# SensorStick.net
KiCad netlist of a schematic drawn in EAGLE
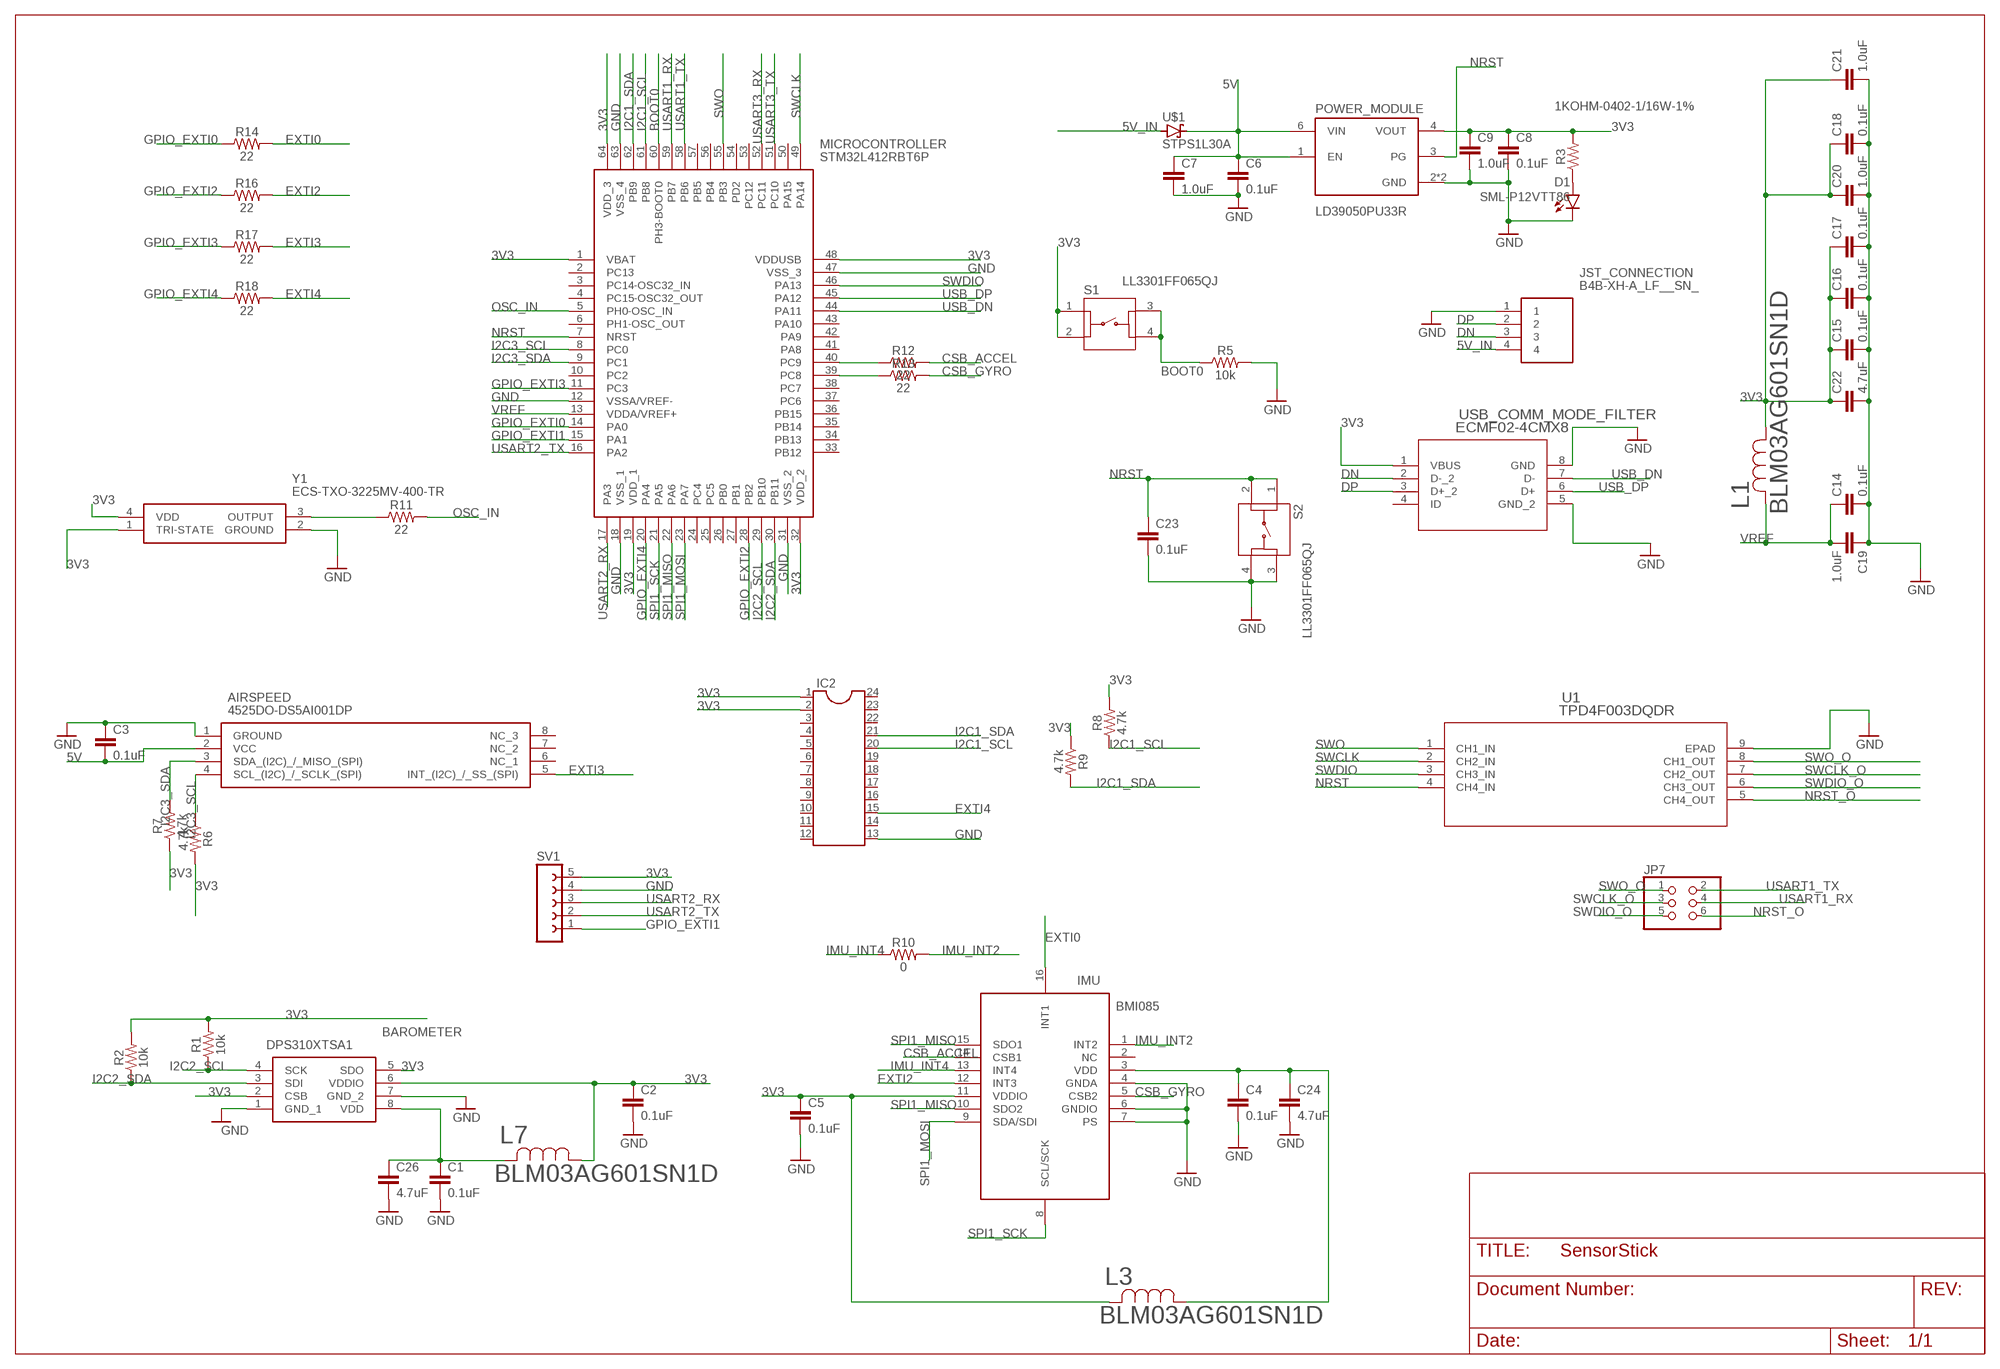
[diagram p0: schematic, sheet 1]

(export (version "E")
  (design (tool "Eeschema 10.0.6"))
  (components
    (comp (ref "AIRSPEED")
      (value "4525DO-DS5AI001DP")
      (footprint "eagle-import:4525DO-DS...P")
      (fields (field (name "MOUSER_PART_NUMBER") "824-4525DODS5AI001DP"))
      (libsource (lib "eagle-import") (part "4525DO-DS5AI001DP"))
    )
    (comp (ref "BAROMETER")
      (value "DPS310XTSA1")
      (footprint "eagle-import:DPS310XTSA1")
      (fields (field (name "MOUSER_PART_NUMBER") "726-DPS310XTSA1"))
      (libsource (lib "eagle-import") (part "DPS310XTSA1"))
    )
    (comp (ref "C1")
      (value "0.1uF")
      (footprint "eagle-import:0402")
      (libsource (lib "eagle-import") (part "0.1UF-0402-6.3V-10%-X7R"))
    )
    (comp (ref "C2")
      (value "0.1uF")
      (footprint "eagle-import:0402")
      (libsource (lib "eagle-import") (part "0.1UF-0402-6.3V-10%-X7R"))
    )
    (comp (ref "C3")
      (value "0.1uF")
      (footprint "eagle-import:0402")
      (fields (field (name "SPICEPREFIX") "C"))
      (libsource (lib "eagle-import") (part "0.1UF-0402-6.3V-10%-X7R"))
    )
    (comp (ref "C4")
      (value "0.1uF")
      (footprint "eagle-import:0402")
      (libsource (lib "eagle-import") (part "0.1UF-0402-6.3V-10%-X7R"))
    )
    (comp (ref "C5")
      (value "0.1uF")
      (footprint "eagle-import:0402")
      (libsource (lib "eagle-import") (part "0.1UF-0402-6.3V-10%-X7R"))
    )
    (comp (ref "C6")
      (value "0.1uF")
      (footprint "eagle-import:0402")
      (libsource (lib "eagle-import") (part "0.1UF-0402-6.3V-10%-X7R"))
    )
    (comp (ref "C7")
      (value "1.0uF")
      (footprint "eagle-import:0402")
      (libsource (lib "eagle-import") (part "1.0UF-0402-16V-10%"))
    )
    (comp (ref "C8")
      (value "0.1uF")
      (footprint "eagle-import:0402")
      (libsource (lib "eagle-import") (part "0.1UF-0402-6.3V-10%-X7R"))
    )
    (comp (ref "C9")
      (value "1.0uF")
      (footprint "eagle-import:0402")
      (libsource (lib "eagle-import") (part "1.0UF-0402-16V-10%"))
    )
    (comp (ref "C14")
      (value "0.1uF")
      (footprint "eagle-import:0603")
      (libsource (lib "eagle-import") (part "SparkFun-Capacitors_510_0.1UF-0603-25V-5%"))
    )
    (comp (ref "C15")
      (value "0.1uF")
      (footprint "eagle-import:0603")
      (libsource (lib "eagle-import") (part "SparkFun-Capacitors_510_0.1UF-0603-25V-5%"))
    )
    (comp (ref "C16")
      (value "0.1uF")
      (footprint "eagle-import:0603")
      (libsource (lib "eagle-import") (part "SparkFun-Capacitors_510_0.1UF-0603-25V-5%"))
    )
    (comp (ref "C17")
      (value "0.1uF")
      (footprint "eagle-import:0603")
      (libsource (lib "eagle-import") (part "SparkFun-Capacitors_510_0.1UF-0603-25V-5%"))
    )
    (comp (ref "C18")
      (value "0.1uF")
      (footprint "eagle-import:0603")
      (libsource (lib "eagle-import") (part "SparkFun-Capacitors_510_0.1UF-0603-25V-5%"))
    )
    (comp (ref "C19")
      (value "1.0uF")
      (footprint "eagle-import:0805")
      (libsource (lib "eagle-import") (part "SparkFun-Capacitors_510_1.0UF-0805-25V-10%"))
    )
    (comp (ref "C20")
      (value "1.0uF")
      (footprint "eagle-import:0805")
      (libsource (lib "eagle-import") (part "SparkFun-Capacitors_510_1.0UF-0805-25V-10%"))
    )
    (comp (ref "C21")
      (value "1.0uF")
      (footprint "eagle-import:0805")
      (libsource (lib "eagle-import") (part "SparkFun-Capacitors_510_1.0UF-0805-25V-10%"))
    )
    (comp (ref "C22")
      (value "4.7uF")
      (footprint "eagle-import:0603")
      (libsource (lib "eagle-import") (part "4.7UF0603"))
    )
    (comp (ref "C23")
      (value "0.1uF")
      (footprint "eagle-import:0603")
      (libsource (lib "eagle-import") (part "SparkFun-Capacitors_510_0.1UF-0603-25V-5%"))
    )
    (comp (ref "C24")
      (value "4.7uF")
      (footprint "eagle-import:0603")
      (libsource (lib "eagle-import") (part "4.7UF0603"))
    )
    (comp (ref "C26")
      (value "4.7uF")
      (footprint "eagle-import:0603")
      (libsource (lib "eagle-import") (part "4.7UF0603"))
    )
    (comp (ref "D1")
      (value "SML-P12VTT86")
      (footprint "eagle-import:LED_SML-P11UTT86R")
      (fields (field (name "MF") "Rohm"))
      (libsource (lib "eagle-import") (part "SML-P12VTT86"))
    )
    (comp (ref "IC2")
      (value "DIL24-6")
      (footprint "eagle-import:DIL24-6")
      (libsource (lib "eagle-import") (part "DIL24-6"))
    )
    (comp (ref "IMU")
      (value "BMI085")
      (footprint "eagle-import:BMI085")
      (fields (field (name "MOUSER_PART_NUMBER") "262-BMI085"))
      (libsource (lib "eagle-import") (part "BMI085"))
    )
    (comp (ref "JP7")
      (value "PINHD-2X3")
      (footprint "eagle-import:2X03")
      (libsource (lib "eagle-import") (part "PINHD-2X3"))
    )
    (comp (ref "JST_CONNECTION")
      (value "B4B-XH-A_LF__SN_")
      (footprint "eagle-import:B4BXHALFSN")
      (fields (field (name "ARROW_PART_NUMBER") "B4B-XH-A(LF)(SN)"))
      (libsource (lib "eagle-import") (part "B4B-XH-A_LF__SN_"))
    )
    (comp (ref "L1")
      (value "BLM03AG601SN1D")
      (footprint "eagle-import:IND_BLM03_0201_MUR")
      (fields (field (name "COPYRIGHT") "Copyright (C) 2023 Ultra Librarian. All rights reserved."))
      (libsource (lib "eagle-import") (part "BLM03AG601SN1D"))
    )
    (comp (ref "L3")
      (value "BLM03AG601SN1D")
      (footprint "eagle-import:IND_BLM03_0201_MUR")
      (fields (field (name "COPYRIGHT") "Copyright (C) 2023 Ultra Librarian. All rights reserved."))
      (libsource (lib "eagle-import") (part "BLM03AG601SN1D"))
    )
    (comp (ref "L7")
      (value "BLM03AG601SN1D")
      (footprint "eagle-import:IND_BLM03_0201_MUR")
      (fields (field (name "COPYRIGHT") "Copyright (C) 2023 Ultra Librarian. All rights reserved."))
      (libsource (lib "eagle-import") (part "BLM03AG601SN1D"))
    )
    (comp (ref "MICROCONTROLLER")
      (value "STM32L412RBT6P")
      (footprint "eagle-import:QFP50P1200X1200X160-64N")
      (fields (field (name "MOUSER_PART_NUMBER") "511-STM32L412RBT6P"))
      (libsource (lib "eagle-import") (part "STM32L412RBT6P"))
    )
    (comp (ref "POWER_MODULE")
      (value "LD39050PU33R")
      (footprint "eagle-import:SON95P300X300X100-7N")
      (fields (field (name "MF") "STMicroelectronics"))
      (libsource (lib "eagle-import") (part "LD39050PU33R"))
    )
    (comp (ref "R1")
      (value "10k")
      (footprint "eagle-import:0402")
      (libsource (lib "eagle-import") (part "10KOHM-0402-1/16W-1%"))
    )
    (comp (ref "R2")
      (value "10k")
      (footprint "eagle-import:0402")
      (libsource (lib "eagle-import") (part "10KOHM-0402-1/16W-1%"))
    )
    (comp (ref "R3")
      (value "1KOHM-0402-1/16W-1%")
      (footprint "eagle-import:0402")
      (libsource (lib "eagle-import") (part "1KOHM-0402-1/16W-1%"))
    )
    (comp (ref "R5")
      (value "10k")
      (footprint "eagle-import:0603")
      (libsource (lib "eagle-import") (part "SparkFun-Resistors_532_10KOHM-0603-1/10W-1%"))
    )
    (comp (ref "R6")
      (value "4.7k")
      (footprint "eagle-import:0603")
      (libsource (lib "eagle-import") (part "4.7KOHM-0603-1/10W-1%"))
    )
    (comp (ref "R7")
      (value "4.7k")
      (footprint "eagle-import:0603")
      (libsource (lib "eagle-import") (part "4.7KOHM-0603-1/10W-1%"))
    )
    (comp (ref "R8")
      (value "4.7k")
      (footprint "eagle-import:0603")
      (libsource (lib "eagle-import") (part "4.7KOHM-0603-1/10W-1%"))
    )
    (comp (ref "R9")
      (value "4.7k")
      (footprint "eagle-import:0603")
      (libsource (lib "eagle-import") (part "4.7KOHM-0603-1/10W-1%"))
    )
    (comp (ref "R10")
      (value "0")
      (footprint "eagle-import:0603")
      (libsource (lib "eagle-import") (part "0OHM-0603-1/10W-5%"))
    )
    (comp (ref "R11")
      (value "22")
      (footprint "eagle-import:0402")
      (libsource (lib "eagle-import") (part "22OHM-0402-1/10W-1%"))
    )
    (comp (ref "R12")
      (value "22")
      (footprint "eagle-import:0402")
      (libsource (lib "eagle-import") (part "22OHM-0402-1/10W-1%"))
    )
    (comp (ref "R13")
      (value "22")
      (footprint "eagle-import:0402")
      (libsource (lib "eagle-import") (part "22OHM-0402-1/10W-1%"))
    )
    (comp (ref "R14")
      (value "22")
      (footprint "eagle-import:0402")
      (libsource (lib "eagle-import") (part "22OHM-0402-1/10W-1%"))
    )
    (comp (ref "R16")
      (value "22")
      (footprint "eagle-import:0402")
      (libsource (lib "eagle-import") (part "22OHM-0402-1/10W-1%"))
    )
    (comp (ref "R17")
      (value "22")
      (footprint "eagle-import:0402")
      (libsource (lib "eagle-import") (part "22OHM-0402-1/10W-1%"))
    )
    (comp (ref "R18")
      (value "22")
      (footprint "eagle-import:0402")
      (libsource (lib "eagle-import") (part "22OHM-0402-1/10W-1%"))
    )
    (comp (ref "S1")
      (value "LL3301FF065QJ")
      (footprint "eagle-import:LL3301FF065QJ")
      (fields (field (name "MOUSER_PART_NUMBER") "612-LL3301FF065QJ"))
      (libsource (lib "eagle-import") (part "LL3301FF065QJ"))
    )
    (comp (ref "S2")
      (value "LL3301FF065QJ")
      (footprint "eagle-import:LL3301FF065QJ")
      (fields (field (name "MOUSER_PART_NUMBER") "612-LL3301FF065QJ"))
      (libsource (lib "eagle-import") (part "LL3301FF065QJ"))
    )
    (comp (ref "SV1")
      (value "FE05-1")
      (footprint "eagle-import:FE05-1")
      (libsource (lib "eagle-import") (part "FE05-1"))
    )
    (comp (ref "U$1")
      (value "STPS1L30A")
      (footprint "eagle-import:DIOM5226X223N")
      (libsource (lib "eagle-import") (part "STPS1L30A"))
    )
    (comp (ref "U1")
      (value "TPD4F003DQDR")
      (footprint "eagle-import:DQD8_1P2X0P4")
      (fields (field (name "COPYRIGHT") "Copyright (C) 2023 Ultra Librarian. All rights reserved."))
      (libsource (lib "eagle-import") (part "TPD4F003DQDR"))
    )
    (comp (ref "USB_COMM_MODE_FILTER")
      (value "ECMF02-4CMX8")
      (footprint "eagle-import:MICRO_QFN-8L_STM")
      (fields (field (name "COPYRIGHT") "Copyright (C) 2023 Ultra Librarian. All rights reserved."))
      (libsource (lib "eagle-import") (part "ECMF02-4CMX8"))
    )
    (comp (ref "Y1")
      (value "ECS-TXO-3225MV-400-TR")
      (footprint "eagle-import:ECSTXO3225MV400TR")
      (libsource (lib "eagle-import") (part "ECS-TXO-3225MV-400-TR"))
    )
  )
  (nets
    (net (code "1") (name "/3V3") (class "Default")
      (node (ref "BAROMETER") (pin "2") (pinfunction "CSB_2") (pintype "bidirectional"))
      (node (ref "BAROMETER") (pin "5") (pinfunction "SDO_5") (pintype "bidirectional"))
      (node (ref "BAROMETER") (pin "6") (pinfunction "VDDIO_6") (pintype "bidirectional"))
      (node (ref "C15") (pin "1") (pinfunction "1_1") (pintype "passive"))
      (node (ref "C16") (pin "1") (pinfunction "1_1") (pintype "passive"))
      (node (ref "C17") (pin "1") (pinfunction "1_1") (pintype "passive"))
      (node (ref "C18") (pin "1") (pinfunction "1_1") (pintype "passive"))
      (node (ref "C2") (pin "1") (pinfunction "1_1") (pintype "passive"))
      (node (ref "C20") (pin "1") (pinfunction "1_1") (pintype "passive"))
      (node (ref "C21") (pin "1") (pinfunction "1_1") (pintype "passive"))
      (node (ref "C22") (pin "1") (pinfunction "1_1") (pintype "passive"))
      (node (ref "C5") (pin "1") (pinfunction "1_1") (pintype "passive"))
      (node (ref "C8") (pin "1") (pinfunction "1_1") (pintype "passive"))
      (node (ref "C9") (pin "1") (pinfunction "1_1") (pintype "passive"))
      (node (ref "IC2") (pin "1") (pinfunction "1_1") (pintype "passive"))
      (node (ref "IC2") (pin "2") (pinfunction "2_2") (pintype "passive"))
      (node (ref "IMU") (pin "11") (pinfunction "VDDIO_11") (pintype "bidirectional"))
      (node (ref "L1") (pin "1") (pinfunction "1_1") (pintype "passive"))
      (node (ref "L3") (pin "2") (pinfunction "2_2") (pintype "passive"))
      (node (ref "L7") (pin "1") (pinfunction "1_1") (pintype "passive"))
      (node (ref "MICROCONTROLLER") (pin "1") (pinfunction "VBAT_1") (pintype "bidirectional"))
      (node (ref "MICROCONTROLLER") (pin "19") (pinfunction "VDD_1_19") (pintype "bidirectional"))
      (node (ref "MICROCONTROLLER") (pin "32") (pinfunction "VDD_2_32") (pintype "bidirectional"))
      (node (ref "MICROCONTROLLER") (pin "48") (pinfunction "VDDUSB_48") (pintype "bidirectional"))
      (node (ref "MICROCONTROLLER") (pin "64") (pinfunction "VDD_3_64") (pintype "bidirectional"))
      (node (ref "POWER_MODULE") (pin "4") (pinfunction "VOUT_4") (pintype "output"))
      (node (ref "R1") (pin "2") (pinfunction "2_2") (pintype "passive"))
      (node (ref "R2") (pin "2") (pinfunction "2_2") (pintype "passive"))
      (node (ref "R3") (pin "2") (pinfunction "2_2") (pintype "passive"))
      (node (ref "R6") (pin "2") (pinfunction "2_2") (pintype "passive"))
      (node (ref "R7") (pin "1") (pinfunction "1_1") (pintype "passive"))
      (node (ref "R8") (pin "2") (pinfunction "2_2") (pintype "passive"))
      (node (ref "R9") (pin "1") (pinfunction "1_1") (pintype "passive"))
      (node (ref "S1") (pin "1") (pinfunction "1_1") (pintype "passive"))
      (node (ref "S1") (pin "2") (pinfunction "2_2") (pintype "passive"))
      (node (ref "SV1") (pin "5") (pinfunction "5_5") (pintype "passive"))
      (node (ref "USB_COMM_MODE_FILTER") (pin "1") (pinfunction "VBUS_1") (pintype "power_in"))
      (node (ref "Y1") (pin "1") (pinfunction "TRI-STATE_1") (pintype "bidirectional"))
      (node (ref "Y1") (pin "4") (pinfunction "VDD_4") (pintype "bidirectional"))
    )
    (net (code "2") (name "/5V") (class "Default")
      (node (ref "AIRSPEED") (pin "2") (pinfunction "VCC_2") (pintype "power_in"))
      (node (ref "C3") (pin "2") (pinfunction "2_2") (pintype "passive"))
      (node (ref "C6") (pin "1") (pinfunction "1_1") (pintype "passive"))
      (node (ref "C7") (pin "1") (pinfunction "1_1") (pintype "passive"))
      (node (ref "POWER_MODULE") (pin "1") (pinfunction "EN_1") (pintype "input"))
      (node (ref "POWER_MODULE") (pin "6") (pinfunction "VIN_6") (pintype "power_in"))
      (node (ref "U$1") (pin "1") (pinfunction "C_1") (pintype "passive"))
    )
    (net (code "3") (name "/5V_IN") (class "Default")
      (node (ref "JST_CONNECTION") (pin "4") (pinfunction "4_4") (pintype "bidirectional"))
      (node (ref "U$1") (pin "2") (pinfunction "A_2") (pintype "passive"))
    )
    (net (code "4") (name "/BOOT0") (class "Default")
      (node (ref "MICROCONTROLLER") (pin "60") (pinfunction "PH3-BOOT0_60") (pintype "bidirectional"))
      (node (ref "R5") (pin "1") (pinfunction "1_1") (pintype "passive"))
      (node (ref "S1") (pin "3") (pinfunction "3_3") (pintype "passive"))
      (node (ref "S1") (pin "4") (pinfunction "4_4") (pintype "passive"))
    )
    (net (code "5") (name "/CSB_ACCEL") (class "Default")
      (node (ref "IMU") (pin "14") (pinfunction "CSB1_14") (pintype "bidirectional"))
      (node (ref "R12") (pin "2") (pinfunction "2_2") (pintype "passive"))
    )
    (net (code "6") (name "/CSB_GYRO") (class "Default")
      (node (ref "IMU") (pin "5") (pinfunction "CSB2_5") (pintype "bidirectional"))
      (node (ref "R13") (pin "2") (pinfunction "2_2") (pintype "passive"))
    )
    (net (code "7") (name "/DN") (class "Default")
      (node (ref "JST_CONNECTION") (pin "3") (pinfunction "3_3") (pintype "bidirectional"))
      (node (ref "USB_COMM_MODE_FILTER") (pin "2") (pinfunction "D-_2_2") (pintype "bidirectional"))
    )
    (net (code "8") (name "/DP") (class "Default")
      (node (ref "JST_CONNECTION") (pin "2") (pinfunction "2_2") (pintype "bidirectional"))
      (node (ref "USB_COMM_MODE_FILTER") (pin "3") (pinfunction "D+_2_3") (pintype "bidirectional"))
    )
    (net (code "9") (name "/EXTI0") (class "Default")
      (node (ref "IMU") (pin "16") (pinfunction "INT1_16") (pintype "bidirectional"))
      (node (ref "R14") (pin "2") (pinfunction "2_2") (pintype "passive"))
    )
    (net (code "10") (name "/EXTI2") (class "Default")
      (node (ref "IMU") (pin "12") (pinfunction "INT3_12") (pintype "bidirectional"))
      (node (ref "R16") (pin "2") (pinfunction "2_2") (pintype "passive"))
    )
    (net (code "11") (name "/EXTI3") (class "Default")
      (node (ref "AIRSPEED") (pin "5") (pinfunction "INT_(I2C)_/_SS_(SPI)_5") (pintype "bidirectional"))
      (node (ref "R17") (pin "2") (pinfunction "2_2") (pintype "passive"))
    )
    (net (code "12") (name "/EXTI4") (class "Default")
      (node (ref "IC2") (pin "15") (pinfunction "15_15") (pintype "passive"))
      (node (ref "R18") (pin "2") (pinfunction "2_2") (pintype "passive"))
    )
    (net (code "13") (name "/GPIO_EXTI0") (class "Default")
      (node (ref "MICROCONTROLLER") (pin "14") (pinfunction "PA0_14") (pintype "bidirectional"))
      (node (ref "R14") (pin "1") (pinfunction "1_1") (pintype "passive"))
    )
    (net (code "14") (name "/GPIO_EXTI1") (class "Default")
      (node (ref "MICROCONTROLLER") (pin "15") (pinfunction "PA1_15") (pintype "bidirectional"))
      (node (ref "SV1") (pin "1") (pinfunction "1_1") (pintype "passive"))
    )
    (net (code "15") (name "/GPIO_EXTI2") (class "Default")
      (node (ref "MICROCONTROLLER") (pin "28") (pinfunction "PB2_28") (pintype "bidirectional"))
      (node (ref "R16") (pin "1") (pinfunction "1_1") (pintype "passive"))
    )
    (net (code "16") (name "/GPIO_EXTI3") (class "Default")
      (node (ref "MICROCONTROLLER") (pin "11") (pinfunction "PC3_11") (pintype "bidirectional"))
      (node (ref "R17") (pin "1") (pinfunction "1_1") (pintype "passive"))
    )
    (net (code "17") (name "/GPIO_EXTI4") (class "Default")
      (node (ref "MICROCONTROLLER") (pin "20") (pinfunction "PA4_20") (pintype "bidirectional"))
      (node (ref "R18") (pin "1") (pinfunction "1_1") (pintype "passive"))
    )
    (net (code "18") (name "/I2C1_SCL") (class "Default")
      (node (ref "IC2") (pin "20") (pinfunction "20_20") (pintype "passive"))
      (node (ref "MICROCONTROLLER") (pin "61") (pinfunction "PB8_61") (pintype "bidirectional"))
      (node (ref "R8") (pin "1") (pinfunction "1_1") (pintype "passive"))
    )
    (net (code "19") (name "/I2C1_SDA") (class "Default")
      (node (ref "IC2") (pin "21") (pinfunction "21_21") (pintype "passive"))
      (node (ref "MICROCONTROLLER") (pin "62") (pinfunction "PB9_62") (pintype "bidirectional"))
      (node (ref "R9") (pin "2") (pinfunction "2_2") (pintype "passive"))
    )
    (net (code "20") (name "/I2C2_SCL") (class "Default")
      (node (ref "BAROMETER") (pin "4") (pinfunction "SCK_4") (pintype "bidirectional"))
      (node (ref "MICROCONTROLLER") (pin "29") (pinfunction "PB10_29") (pintype "bidirectional"))
      (node (ref "R1") (pin "1") (pinfunction "1_1") (pintype "passive"))
    )
    (net (code "21") (name "/I2C2_SDA") (class "Default")
      (node (ref "BAROMETER") (pin "3") (pinfunction "SDI_3") (pintype "bidirectional"))
      (node (ref "MICROCONTROLLER") (pin "30") (pinfunction "PB11_30") (pintype "bidirectional"))
      (node (ref "R2") (pin "1") (pinfunction "1_1") (pintype "passive"))
    )
    (net (code "22") (name "/I2C3_SCL") (class "Default")
      (node (ref "AIRSPEED") (pin "4") (pinfunction "SCL_(I2C)_/_SCLK_(SPI)_4") (pintype "bidirectional"))
      (node (ref "MICROCONTROLLER") (pin "8") (pinfunction "PC0_8") (pintype "bidirectional"))
      (node (ref "R6") (pin "1") (pinfunction "1_1") (pintype "passive"))
    )
    (net (code "23") (name "/I2C3_SDA") (class "Default")
      (node (ref "AIRSPEED") (pin "3") (pinfunction "SDA_(I2C)_/_MISO_(SPI)_3") (pintype "bidirectional"))
      (node (ref "MICROCONTROLLER") (pin "9") (pinfunction "PC1_9") (pintype "bidirectional"))
      (node (ref "R7") (pin "2") (pinfunction "2_2") (pintype "passive"))
    )
    (net (code "24") (name "/IMU_INT2") (class "Default")
      (node (ref "IMU") (pin "1") (pinfunction "INT2_1") (pintype "bidirectional"))
      (node (ref "R10") (pin "2") (pinfunction "2_2") (pintype "passive"))
    )
    (net (code "25") (name "/IMU_INT4") (class "Default")
      (node (ref "IMU") (pin "13") (pinfunction "INT4_13") (pintype "bidirectional"))
      (node (ref "R10") (pin "1") (pinfunction "1_1") (pintype "passive"))
    )
    (net (code "26") (name "/NRST") (class "Default")
      (node (ref "C23") (pin "1") (pinfunction "1_1") (pintype "passive"))
      (node (ref "MICROCONTROLLER") (pin "7") (pinfunction "NRST_7") (pintype "bidirectional"))
      (node (ref "POWER_MODULE") (pin "3") (pinfunction "PG_3") (pintype "bidirectional"))
      (node (ref "S2") (pin "1") (pinfunction "1_1") (pintype "passive"))
      (node (ref "S2") (pin "2") (pinfunction "2_2") (pintype "passive"))
      (node (ref "U1") (pin "4") (pinfunction "CH4_IN_4") (pintype "input"))
    )
    (net (code "27") (name "/NRST_O") (class "Default")
      (node (ref "JP7") (pin "6") (pinfunction "6_6") (pintype "passive"))
      (node (ref "U1") (pin "5") (pinfunction "CH4_OUT_5") (pintype "output"))
    )
    (net (code "28") (name "/OSC_IN") (class "Default")
      (node (ref "MICROCONTROLLER") (pin "5") (pinfunction "PH0-OSC_IN_5") (pintype "bidirectional"))
      (node (ref "R11") (pin "2") (pinfunction "2_2") (pintype "passive"))
    )
    (net (code "29") (name "/SPI1_MISO") (class "Default")
      (node (ref "IMU") (pin "10") (pinfunction "SDO2_10") (pintype "bidirectional"))
      (node (ref "IMU") (pin "15") (pinfunction "SDO1_15") (pintype "bidirectional"))
      (node (ref "MICROCONTROLLER") (pin "22") (pinfunction "PA6_22") (pintype "bidirectional"))
    )
    (net (code "30") (name "/SPI1_MOSI") (class "Default")
      (node (ref "IMU") (pin "9") (pinfunction "SDA/SDI_9") (pintype "bidirectional"))
      (node (ref "MICROCONTROLLER") (pin "23") (pinfunction "PA7_23") (pintype "bidirectional"))
    )
    (net (code "31") (name "/SPI1_SCK") (class "Default")
      (node (ref "IMU") (pin "8") (pinfunction "SCL/SCK_8") (pintype "bidirectional"))
      (node (ref "MICROCONTROLLER") (pin "21") (pinfunction "PA5_21") (pintype "bidirectional"))
    )
    (net (code "32") (name "/SWCLK") (class "Default")
      (node (ref "MICROCONTROLLER") (pin "49") (pinfunction "PA14_49") (pintype "bidirectional"))
      (node (ref "U1") (pin "2") (pinfunction "CH2_IN_2") (pintype "input"))
    )
    (net (code "33") (name "/SWCLK_O") (class "Default")
      (node (ref "JP7") (pin "3") (pinfunction "3_3") (pintype "passive"))
      (node (ref "U1") (pin "7") (pinfunction "CH2_OUT_7") (pintype "output"))
    )
    (net (code "34") (name "/SWDIO") (class "Default")
      (node (ref "MICROCONTROLLER") (pin "46") (pinfunction "PA13_46") (pintype "bidirectional"))
      (node (ref "U1") (pin "3") (pinfunction "CH3_IN_3") (pintype "input"))
    )
    (net (code "35") (name "/SWDIO_O") (class "Default")
      (node (ref "JP7") (pin "5") (pinfunction "5_5") (pintype "passive"))
      (node (ref "U1") (pin "6") (pinfunction "CH3_OUT_6") (pintype "output"))
    )
    (net (code "36") (name "/SWO") (class "Default")
      (node (ref "MICROCONTROLLER") (pin "55") (pinfunction "PB3_55") (pintype "bidirectional"))
      (node (ref "U1") (pin "1") (pinfunction "CH1_IN_1") (pintype "input"))
    )
    (net (code "37") (name "/SWO_O") (class "Default")
      (node (ref "JP7") (pin "1") (pinfunction "1_1") (pintype "passive"))
      (node (ref "U1") (pin "8") (pinfunction "CH1_OUT_8") (pintype "output"))
    )
    (net (code "38") (name "/USART1_RX") (class "Default")
      (node (ref "JP7") (pin "4") (pinfunction "4_4") (pintype "passive"))
      (node (ref "MICROCONTROLLER") (pin "59") (pinfunction "PB7_59") (pintype "bidirectional"))
    )
    (net (code "39") (name "/USART1_TX") (class "Default")
      (node (ref "JP7") (pin "2") (pinfunction "2_2") (pintype "passive"))
      (node (ref "MICROCONTROLLER") (pin "58") (pinfunction "PB6_58") (pintype "bidirectional"))
    )
    (net (code "40") (name "/USART2_RX") (class "Default")
      (node (ref "MICROCONTROLLER") (pin "17") (pinfunction "PA3_17") (pintype "bidirectional"))
      (node (ref "SV1") (pin "3") (pinfunction "3_3") (pintype "passive"))
    )
    (net (code "41") (name "/USART2_TX") (class "Default")
      (node (ref "MICROCONTROLLER") (pin "16") (pinfunction "PA2_16") (pintype "bidirectional"))
      (node (ref "SV1") (pin "2") (pinfunction "2_2") (pintype "passive"))
    )
    (net (code "42") (name "/USART3_RX") (class "Default")
      (node (ref "MICROCONTROLLER") (pin "52") (pinfunction "PC11_52") (pintype "bidirectional"))
    )
    (net (code "43") (name "/USART3_TX") (class "Default")
      (node (ref "MICROCONTROLLER") (pin "51") (pinfunction "PC10_51") (pintype "bidirectional"))
    )
    (net (code "44") (name "/USB_DN") (class "Default")
      (node (ref "MICROCONTROLLER") (pin "44") (pinfunction "PA11_44") (pintype "bidirectional"))
      (node (ref "USB_COMM_MODE_FILTER") (pin "7") (pinfunction "D-_7") (pintype "bidirectional"))
    )
    (net (code "45") (name "/USB_DP") (class "Default")
      (node (ref "MICROCONTROLLER") (pin "45") (pinfunction "PA12_45") (pintype "bidirectional"))
      (node (ref "USB_COMM_MODE_FILTER") (pin "6") (pinfunction "D+_6") (pintype "bidirectional"))
    )
    (net (code "46") (name "/VREF") (class "Default")
      (node (ref "C14") (pin "1") (pinfunction "1_1") (pintype "passive"))
      (node (ref "C19") (pin "2") (pinfunction "2_2") (pintype "passive"))
      (node (ref "L1") (pin "2") (pinfunction "2_2") (pintype "passive"))
      (node (ref "MICROCONTROLLER") (pin "13") (pinfunction "VDDA/VREF+_13") (pintype "bidirectional"))
    )
    (net (code "47") (name "GND") (class "Default")
      (node (ref "AIRSPEED") (pin "1") (pinfunction "GROUND_1") (pintype "power_in"))
      (node (ref "BAROMETER") (pin "1") (pinfunction "GND_1_1") (pintype "bidirectional"))
      (node (ref "BAROMETER") (pin "7") (pinfunction "GND_2_7") (pintype "bidirectional"))
      (node (ref "C1") (pin "2") (pinfunction "2_2") (pintype "passive"))
      (node (ref "C14") (pin "2") (pinfunction "2_2") (pintype "passive"))
      (node (ref "C15") (pin "2") (pinfunction "2_2") (pintype "passive"))
      (node (ref "C16") (pin "2") (pinfunction "2_2") (pintype "passive"))
      (node (ref "C17") (pin "2") (pinfunction "2_2") (pintype "passive"))
      (node (ref "C18") (pin "2") (pinfunction "2_2") (pintype "passive"))
      (node (ref "C19") (pin "1") (pinfunction "1_1") (pintype "passive"))
      (node (ref "C2") (pin "2") (pinfunction "2_2") (pintype "passive"))
      (node (ref "C20") (pin "2") (pinfunction "2_2") (pintype "passive"))
      (node (ref "C21") (pin "2") (pinfunction "2_2") (pintype "passive"))
      (node (ref "C22") (pin "2") (pinfunction "2_2") (pintype "passive"))
      (node (ref "C23") (pin "2") (pinfunction "2_2") (pintype "passive"))
      (node (ref "C24") (pin "2") (pinfunction "2_2") (pintype "passive"))
      (node (ref "C26") (pin "2") (pinfunction "2_2") (pintype "passive"))
      (node (ref "C3") (pin "1") (pinfunction "1_1") (pintype "passive"))
      (node (ref "C4") (pin "2") (pinfunction "2_2") (pintype "passive"))
      (node (ref "C5") (pin "2") (pinfunction "2_2") (pintype "passive"))
      (node (ref "C6") (pin "2") (pinfunction "2_2") (pintype "passive"))
      (node (ref "C7") (pin "2") (pinfunction "2_2") (pintype "passive"))
      (node (ref "C8") (pin "2") (pinfunction "2_2") (pintype "passive"))
      (node (ref "C9") (pin "2") (pinfunction "2_2") (pintype "passive"))
      (node (ref "D1") (pin "C") (pinfunction "C_C") (pintype "passive"))
      (node (ref "IC2") (pin "13") (pinfunction "13_13") (pintype "passive"))
      (node (ref "IMU") (pin "4") (pinfunction "GNDA_4") (pintype "bidirectional"))
      (node (ref "IMU") (pin "6") (pinfunction "GNDIO_6") (pintype "bidirectional"))
      (node (ref "IMU") (pin "7") (pinfunction "PS_7") (pintype "bidirectional"))
      (node (ref "JST_CONNECTION") (pin "1") (pinfunction "1_1") (pintype "bidirectional"))
      (node (ref "MICROCONTROLLER") (pin "12") (pinfunction "VSSA/VREF-_12") (pintype "bidirectional"))
      (node (ref "MICROCONTROLLER") (pin "18") (pinfunction "VSS_1_18") (pintype "bidirectional"))
      (node (ref "MICROCONTROLLER") (pin "31") (pinfunction "VSS_2_31") (pintype "bidirectional"))
      (node (ref "MICROCONTROLLER") (pin "47") (pinfunction "VSS_3_47") (pintype "bidirectional"))
      (node (ref "MICROCONTROLLER") (pin "63") (pinfunction "VSS_4_63") (pintype "bidirectional"))
      (node (ref "POWER_MODULE") (pin "2") (pinfunction "GND_2") (pintype "power_in"))
      (node (ref "POWER_MODULE") (pin "7") (pinfunction "GND_7") (pintype "power_in"))
      (node (ref "R5") (pin "2") (pinfunction "2_2") (pintype "passive"))
      (node (ref "S2") (pin "3") (pinfunction "3_3") (pintype "passive"))
      (node (ref "S2") (pin "4") (pinfunction "4_4") (pintype "passive"))
      (node (ref "SV1") (pin "4") (pinfunction "4_4") (pintype "passive"))
      (node (ref "U1") (pin "9") (pinfunction "EPAD_9") (pintype "passive"))
      (node (ref "USB_COMM_MODE_FILTER") (pin "5") (pinfunction "GND_2_5") (pintype "passive"))
      (node (ref "USB_COMM_MODE_FILTER") (pin "8") (pinfunction "GND_8") (pintype "passive"))
      (node (ref "Y1") (pin "2") (pinfunction "GROUND_2") (pintype "bidirectional"))
    )
    (net (code "48") (name "Net-(BAROMETER-VDD)") (class "Default")
      (node (ref "BAROMETER") (pin "8") (pinfunction "VDD_8") (pintype "bidirectional"))
      (node (ref "C1") (pin "1") (pinfunction "1_1") (pintype "passive"))
      (node (ref "C26") (pin "1") (pinfunction "1_1") (pintype "passive"))
      (node (ref "L7") (pin "2") (pinfunction "2_2") (pintype "passive"))
    )
    (net (code "49") (name "Net-(D1-PadA)") (class "Default")
      (node (ref "D1") (pin "A") (pinfunction "A_A") (pintype "passive"))
      (node (ref "R3") (pin "1") (pinfunction "1_1") (pintype "passive"))
    )
    (net (code "50") (name "Net-(IMU-VDD)") (class "Default")
      (node (ref "C24") (pin "1") (pinfunction "1_1") (pintype "passive"))
      (node (ref "C4") (pin "1") (pinfunction "1_1") (pintype "passive"))
      (node (ref "IMU") (pin "3") (pinfunction "VDD_3") (pintype "bidirectional"))
      (node (ref "L3") (pin "1") (pinfunction "1_1") (pintype "passive"))
    )
    (net (code "51") (name "Net-(MICROCONTROLLER-PC8)") (class "Default")
      (node (ref "MICROCONTROLLER") (pin "39") (pinfunction "PC8_39") (pintype "bidirectional"))
      (node (ref "R13") (pin "1") (pinfunction "1_1") (pintype "passive"))
    )
    (net (code "52") (name "Net-(MICROCONTROLLER-PC9)") (class "Default")
      (node (ref "MICROCONTROLLER") (pin "40") (pinfunction "PC9_40") (pintype "bidirectional"))
      (node (ref "R12") (pin "1") (pinfunction "1_1") (pintype "passive"))
    )
    (net (code "53") (name "Net-(Y1-OUTPUT)") (class "Default")
      (node (ref "R11") (pin "1") (pinfunction "1_1") (pintype "passive"))
      (node (ref "Y1") (pin "3") (pinfunction "OUTPUT_3") (pintype "bidirectional"))
    )
    (net (code "54") (name "unconnected-(AIRSPEED-NC_1-Pad6)") (class "Default")
      (node (ref "AIRSPEED") (pin "6") (pinfunction "NC_1_6") (pintype "bidirectional"))
    )
    (net (code "55") (name "unconnected-(AIRSPEED-NC_2-Pad7)") (class "Default")
      (node (ref "AIRSPEED") (pin "7") (pinfunction "NC_2_7") (pintype "bidirectional"))
    )
    (net (code "56") (name "unconnected-(AIRSPEED-NC_3-Pad8)") (class "Default")
      (node (ref "AIRSPEED") (pin "8") (pinfunction "NC_3_8") (pintype "bidirectional"))
    )
    (net (code "57") (name "unconnected-(IC2-Pad3)") (class "Default")
      (node (ref "IC2") (pin "3") (pinfunction "3_3") (pintype "passive"))
    )
    (net (code "58") (name "unconnected-(IC2-Pad4)") (class "Default")
      (node (ref "IC2") (pin "4") (pinfunction "4_4") (pintype "passive"))
    )
    (net (code "59") (name "unconnected-(IC2-Pad5)") (class "Default")
      (node (ref "IC2") (pin "5") (pinfunction "5_5") (pintype "passive"))
    )
    (net (code "60") (name "unconnected-(IC2-Pad6)") (class "Default")
      (node (ref "IC2") (pin "6") (pinfunction "6_6") (pintype "passive"))
    )
    (net (code "61") (name "unconnected-(IC2-Pad7)") (class "Default")
      (node (ref "IC2") (pin "7") (pinfunction "7_7") (pintype "passive"))
    )
    (net (code "62") (name "unconnected-(IC2-Pad8)") (class "Default")
      (node (ref "IC2") (pin "8") (pinfunction "8_8") (pintype "passive"))
    )
    (net (code "63") (name "unconnected-(IC2-Pad9)") (class "Default")
      (node (ref "IC2") (pin "9") (pinfunction "9_9") (pintype "passive"))
    )
    (net (code "64") (name "unconnected-(IC2-Pad10)") (class "Default")
      (node (ref "IC2") (pin "10") (pinfunction "10_10") (pintype "passive"))
    )
    (net (code "65") (name "unconnected-(IC2-Pad11)") (class "Default")
      (node (ref "IC2") (pin "11") (pinfunction "11_11") (pintype "passive"))
    )
    (net (code "66") (name "unconnected-(IC2-Pad12)") (class "Default")
      (node (ref "IC2") (pin "12") (pinfunction "12_12") (pintype "passive"))
    )
    (net (code "67") (name "unconnected-(IC2-Pad14)") (class "Default")
      (node (ref "IC2") (pin "14") (pinfunction "14_14") (pintype "passive"))
    )
    (net (code "68") (name "unconnected-(IC2-Pad16)") (class "Default")
      (node (ref "IC2") (pin "16") (pinfunction "16_16") (pintype "passive"))
    )
    (net (code "69") (name "unconnected-(IC2-Pad17)") (class "Default")
      (node (ref "IC2") (pin "17") (pinfunction "17_17") (pintype "passive"))
    )
    (net (code "70") (name "unconnected-(IC2-Pad18)") (class "Default")
      (node (ref "IC2") (pin "18") (pinfunction "18_18") (pintype "passive"))
    )
    (net (code "71") (name "unconnected-(IC2-Pad19)") (class "Default")
      (node (ref "IC2") (pin "19") (pinfunction "19_19") (pintype "passive"))
    )
    (net (code "72") (name "unconnected-(IC2-Pad22)") (class "Default")
      (node (ref "IC2") (pin "22") (pinfunction "22_22") (pintype "passive"))
    )
    (net (code "73") (name "unconnected-(IC2-Pad23)") (class "Default")
      (node (ref "IC2") (pin "23") (pinfunction "23_23") (pintype "passive"))
    )
    (net (code "74") (name "unconnected-(IC2-Pad24)") (class "Default")
      (node (ref "IC2") (pin "24") (pinfunction "24_24") (pintype "passive"))
    )
    (net (code "75") (name "unconnected-(IMU-NC-Pad2)") (class "Default")
      (node (ref "IMU") (pin "2") (pinfunction "NC_2") (pintype "no_connect"))
    )
    (net (code "76") (name "unconnected-(MICROCONTROLLER-PA8-Pad41)") (class "Default")
      (node (ref "MICROCONTROLLER") (pin "41") (pinfunction "PA8_41") (pintype "bidirectional"))
    )
    (net (code "77") (name "unconnected-(MICROCONTROLLER-PA9-Pad42)") (class "Default")
      (node (ref "MICROCONTROLLER") (pin "42") (pinfunction "PA9_42") (pintype "bidirectional"))
    )
    (net (code "78") (name "unconnected-(MICROCONTROLLER-PA10-Pad43)") (class "Default")
      (node (ref "MICROCONTROLLER") (pin "43") (pinfunction "PA10_43") (pintype "bidirectional"))
    )
    (net (code "79") (name "unconnected-(MICROCONTROLLER-PA15-Pad50)") (class "Default")
      (node (ref "MICROCONTROLLER") (pin "50") (pinfunction "PA15_50") (pintype "bidirectional"))
    )
    (net (code "80") (name "unconnected-(MICROCONTROLLER-PB0-Pad26)") (class "Default")
      (node (ref "MICROCONTROLLER") (pin "26") (pinfunction "PB0_26") (pintype "bidirectional"))
    )
    (net (code "81") (name "unconnected-(MICROCONTROLLER-PB1-Pad27)") (class "Default")
      (node (ref "MICROCONTROLLER") (pin "27") (pinfunction "PB1_27") (pintype "bidirectional"))
    )
    (net (code "82") (name "unconnected-(MICROCONTROLLER-PB4-Pad56)") (class "Default")
      (node (ref "MICROCONTROLLER") (pin "56") (pinfunction "PB4_56") (pintype "bidirectional"))
    )
    (net (code "83") (name "unconnected-(MICROCONTROLLER-PB5-Pad57)") (class "Default")
      (node (ref "MICROCONTROLLER") (pin "57") (pinfunction "PB5_57") (pintype "bidirectional"))
    )
    (net (code "84") (name "unconnected-(MICROCONTROLLER-PB12-Pad33)") (class "Default")
      (node (ref "MICROCONTROLLER") (pin "33") (pinfunction "PB12_33") (pintype "bidirectional"))
    )
    (net (code "85") (name "unconnected-(MICROCONTROLLER-PB13-Pad34)") (class "Default")
      (node (ref "MICROCONTROLLER") (pin "34") (pinfunction "PB13_34") (pintype "bidirectional"))
    )
    (net (code "86") (name "unconnected-(MICROCONTROLLER-PB14-Pad35)") (class "Default")
      (node (ref "MICROCONTROLLER") (pin "35") (pinfunction "PB14_35") (pintype "bidirectional"))
    )
    (net (code "87") (name "unconnected-(MICROCONTROLLER-PB15-Pad36)") (class "Default")
      (node (ref "MICROCONTROLLER") (pin "36") (pinfunction "PB15_36") (pintype "bidirectional"))
    )
    (net (code "88") (name "unconnected-(MICROCONTROLLER-PC2-Pad10)") (class "Default")
      (node (ref "MICROCONTROLLER") (pin "10") (pinfunction "PC2_10") (pintype "bidirectional"))
    )
    (net (code "89") (name "unconnected-(MICROCONTROLLER-PC4-Pad24)") (class "Default")
      (node (ref "MICROCONTROLLER") (pin "24") (pinfunction "PC4_24") (pintype "bidirectional"))
    )
    (net (code "90") (name "unconnected-(MICROCONTROLLER-PC5-Pad25)") (class "Default")
      (node (ref "MICROCONTROLLER") (pin "25") (pinfunction "PC5_25") (pintype "bidirectional"))
    )
    (net (code "91") (name "unconnected-(MICROCONTROLLER-PC6-Pad37)") (class "Default")
      (node (ref "MICROCONTROLLER") (pin "37") (pinfunction "PC6_37") (pintype "bidirectional"))
    )
    (net (code "92") (name "unconnected-(MICROCONTROLLER-PC7-Pad38)") (class "Default")
      (node (ref "MICROCONTROLLER") (pin "38") (pinfunction "PC7_38") (pintype "bidirectional"))
    )
    (net (code "93") (name "unconnected-(MICROCONTROLLER-PC12-Pad53)") (class "Default")
      (node (ref "MICROCONTROLLER") (pin "53") (pinfunction "PC12_53") (pintype "bidirectional"))
    )
    (net (code "94") (name "unconnected-(MICROCONTROLLER-PC13-Pad2)") (class "Default")
      (node (ref "MICROCONTROLLER") (pin "2") (pinfunction "PC13_2") (pintype "bidirectional"))
    )
    (net (code "95") (name "unconnected-(MICROCONTROLLER-PC14-OSC32_IN-Pad3)") (class "Default")
      (node (ref "MICROCONTROLLER") (pin "3") (pinfunction "PC14-OSC32_IN_3") (pintype "bidirectional"))
    )
    (net (code "96") (name "unconnected-(MICROCONTROLLER-PC15-OSC32_OUT-Pad4)") (class "Default")
      (node (ref "MICROCONTROLLER") (pin "4") (pinfunction "PC15-OSC32_OUT_4") (pintype "bidirectional"))
    )
    (net (code "97") (name "unconnected-(MICROCONTROLLER-PD2-Pad54)") (class "Default")
      (node (ref "MICROCONTROLLER") (pin "54") (pinfunction "PD2_54") (pintype "bidirectional"))
    )
    (net (code "98") (name "unconnected-(MICROCONTROLLER-PH1-OSC_OUT-Pad6)") (class "Default")
      (node (ref "MICROCONTROLLER") (pin "6") (pinfunction "PH1-OSC_OUT_6") (pintype "bidirectional"))
    )
    (net (code "99") (name "unconnected-(USB_COMM_MODE_FILTER-ID-Pad4)") (class "Default")
      (node (ref "USB_COMM_MODE_FILTER") (pin "4") (pinfunction "ID_4") (pintype "passive"))
    )
  )
)
